# 3_3V_Regulator.net
KiCad netlist of a schematic drawn in Altium Designer
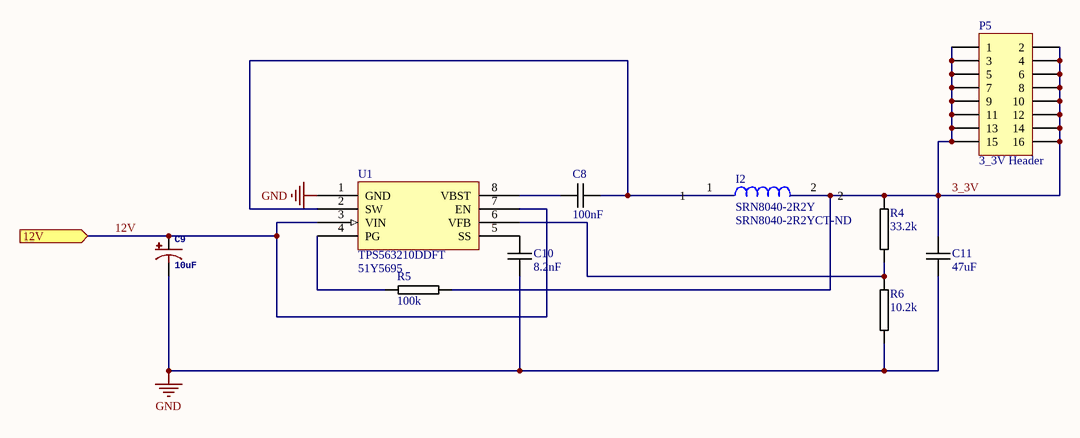
[diagram p0: 3_3V Regulator.SchDoc]

(export (version "E")
  (design (tool "Eeschema 10.0.6"))
  (components
    (comp (ref "C8")
      (value "100nF")
      (footprint "0805C-TBD")
      (description "CAPACITOR 0805 CERAMIC")
      (fields
        (field (name "MANUFACTURER PART NUMBER") "ECJ-1VB0J225K")
        (field (name "MANUFACTURER") "Panasonic - ECG")
      )
      (libsource (lib "vh_altium_library") (part "0603C-2U2-6V3-X5R-PAN"))
    )
    (comp (ref "C9")
      (value "10uF")
      (footprint "EIA3216")
      (libsource (lib "SparkFun-Retired") (part "10UF-TANT"))
    )
    (comp (ref "C10")
      (value "8.2nF")
      (footprint "0603C-GENERIC")
      (description "CAPACITOR 0603 CERAMIC")
      (libsource (lib "vh_altium_library") (part "0603C-000"))
    )
    (comp (ref "C11")
      (value "47uF")
      (footprint "0805C-TBD")
      (description "CAPACITOR 0805 CERAMIC")
      (fields
        (field (name "MANUFACTURER PART NUMBER") "ECJ-1VB0J225K")
        (field (name "MANUFACTURER") "Panasonic - ECG")
      )
      (libsource (lib "vh_altium_library") (part "0603C-2U2-6V3-X5R-PAN"))
    )
    (comp (ref "I2")
      (value "SRN8040-2R2Y")
      (footprint "SRN8040")
      (description "FIXED IND 2.2UH 6.3A 13 MOHM SMD")
      (fields
        (field (name "MANUFACTURER") "Bourns Inc.")
        (field (name "TOLERANCE") "±30%")
        (field (name "SUPPLIER PART NUMBER 1") "SRN8040-2R2YCT-ND")
      )
      (libsource (lib "Digi_Key") (part "SRN8040-2R2Y"))
    )
    (comp (ref "P5")
      (value "3_3V Header")
      (footprint "HDR2X8H")
      (description "Header, 8-Pin, Dual row, Right Angle")
      (fields (field (name "PUBLISHER") "Altium Limited"))
      (libsource (lib "Miscellaneous Connectors") (part "Header 8X2H"))
    )
    (comp (ref "R4")
      (value "33.2k")
      (footprint "0402R-TBD")
      (description "RESISTOR 0402 VALUE TO BE DETERMINED")
      (libsource (lib "vh_altium_library") (part "0402R-TBD"))
    )
    (comp (ref "R5")
      (value "100k")
      (footprint "0402R-TBD")
      (description "RESISTOR 0402 VALUE TO BE DETERMINED")
      (libsource (lib "vh_altium_library") (part "0402R-TBD"))
    )
    (comp (ref "R6")
      (value "10.2k")
      (footprint "0402R-TBD")
      (description "RESISTOR 0402 VALUE TO BE DETERMINED")
      (libsource (lib "vh_altium_library") (part "0402R-TBD"))
    )
    (comp (ref "U1")
      (value "TPS563210DDFT")
      (footprint "vh_altium_library:SOT23-8")
      (description "TEXAS INSTRUMENTS - TPS563210DDFT - DC/DC CONV, SYNC BUCK, 650KHZ, SOT-23-8")
      (fields
        (field (name "MANUFACTURER") "TEXAS INSTRUMENTS")
        (field (name "SUPPLIER PART NUMBER 1") "51Y5695")
      )
      (libsource (lib "Digi_Key") (part "TPS563210DDFT"))
    )
  )
  (nets
    (net (code "1") (name "/3_3V") (class "Default")
      (node (ref "C11") (pin "2") (pintype "passive"))
      (node (ref "I2") (pin "2") (pinfunction "2_2") (pintype "passive"))
      (node (ref "P5") (pin "1") (pinfunction "1_1") (pintype "passive"))
      (node (ref "P5") (pin "10") (pinfunction "10_10") (pintype "passive"))
      (node (ref "P5") (pin "11") (pinfunction "11_11") (pintype "passive"))
      (node (ref "P5") (pin "12") (pinfunction "12_12") (pintype "passive"))
      (node (ref "P5") (pin "13") (pinfunction "13_13") (pintype "passive"))
      (node (ref "P5") (pin "14") (pinfunction "14_14") (pintype "passive"))
      (node (ref "P5") (pin "15") (pinfunction "15_15") (pintype "passive"))
      (node (ref "P5") (pin "16") (pinfunction "16_16") (pintype "passive"))
      (node (ref "P5") (pin "2") (pinfunction "2_2") (pintype "passive"))
      (node (ref "P5") (pin "3") (pinfunction "3_3") (pintype "passive"))
      (node (ref "P5") (pin "4") (pinfunction "4_4") (pintype "passive"))
      (node (ref "P5") (pin "5") (pinfunction "5_5") (pintype "passive"))
      (node (ref "P5") (pin "6") (pinfunction "6_6") (pintype "passive"))
      (node (ref "P5") (pin "7") (pinfunction "7_7") (pintype "passive"))
      (node (ref "P5") (pin "8") (pinfunction "8_8") (pintype "passive"))
      (node (ref "P5") (pin "9") (pinfunction "9_9") (pintype "passive"))
      (node (ref "R4") (pin "1") (pintype "passive"))
      (node (ref "R5") (pin "2") (pintype "passive"))
    )
    (net (code "2") (name "/12V") (class "Default")
      (node (ref "C9") (pin "A") (pinfunction "+_A") (pintype "passive"))
      (node (ref "U1") (pin "3") (pinfunction "VIN_3") (pintype "input"))
      (node (ref "U1") (pin "7") (pinfunction "EN_7") (pintype "passive"))
    )
    (net (code "3") (name "GND") (class "Default")
      (node (ref "C10") (pin "2") (pintype "passive"))
      (node (ref "C11") (pin "1") (pintype "passive"))
      (node (ref "C9") (pin "C") (pinfunction "-_C") (pintype "passive"))
      (node (ref "R6") (pin "2") (pintype "passive"))
      (node (ref "U1") (pin "1") (pinfunction "GND_1") (pintype "passive"))
    )
    (net (code "4") (name "Net-(U1-PG)") (class "Default")
      (node (ref "R5") (pin "1") (pintype "passive"))
      (node (ref "U1") (pin "4") (pinfunction "PG_4") (pintype "passive"))
    )
    (net (code "5") (name "Net-(U1-SS)") (class "Default")
      (node (ref "C10") (pin "1") (pintype "passive"))
      (node (ref "U1") (pin "5") (pinfunction "SS_5") (pintype "passive"))
    )
    (net (code "6") (name "Net-(U1-SW)") (class "Default")
      (node (ref "C8") (pin "2") (pintype "passive"))
      (node (ref "I2") (pin "1") (pinfunction "1_1") (pintype "passive"))
      (node (ref "U1") (pin "2") (pinfunction "SW_2") (pintype "passive"))
    )
    (net (code "7") (name "Net-(U1-VBST)") (class "Default")
      (node (ref "C8") (pin "1") (pintype "passive"))
      (node (ref "U1") (pin "8") (pinfunction "VBST_8") (pintype "passive"))
    )
    (net (code "8") (name "Net-(U1-VFB)") (class "Default")
      (node (ref "R4") (pin "2") (pintype "passive"))
      (node (ref "R6") (pin "1") (pintype "passive"))
      (node (ref "U1") (pin "6") (pinfunction "VFB_6") (pintype "passive"))
    )
  )
)
